# filter.net
KiCad netlist of a schematic drawn in EAGLE
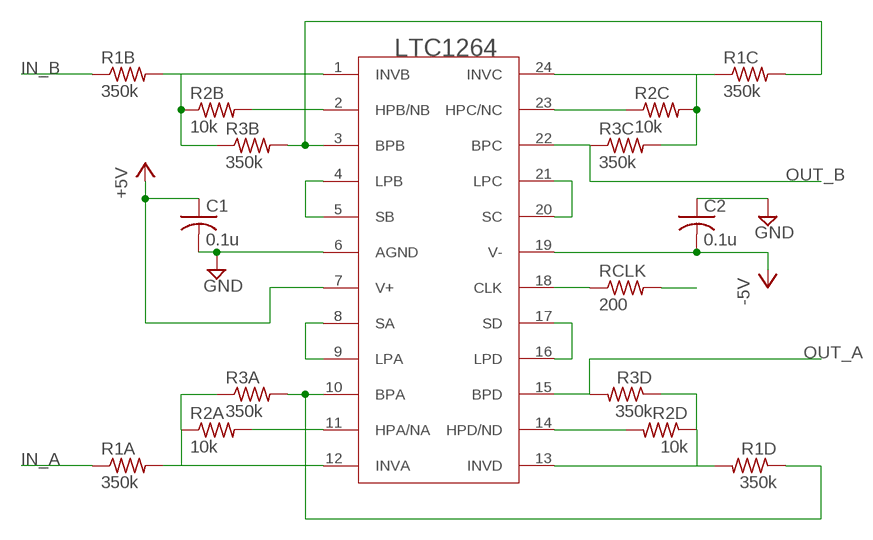
[diagram p0: schematic, sheet 1]

(export (version "E")
  (design (tool "Eeschema 10.0.6"))
  (components
    (comp (ref "C1")
      (value "0.1u")
      (footprint "eagle-import:C0805")
      (libsource (lib "eagle-import") (part "C-USC0805"))
    )
    (comp (ref "C2")
      (value "0.1u")
      (footprint "eagle-import:C0805")
      (libsource (lib "eagle-import") (part "C-USC0805"))
    )
    (comp (ref "R1A")
      (value "350k")
      (footprint "eagle-import:R0805")
      (libsource (lib "eagle-import") (part "R-US_R0805"))
    )
    (comp (ref "R1B")
      (value "350k")
      (footprint "eagle-import:R0805")
      (libsource (lib "eagle-import") (part "R-US_R0805"))
    )
    (comp (ref "R1C")
      (value "350k")
      (footprint "eagle-import:R0805")
      (libsource (lib "eagle-import") (part "R-US_R0805"))
    )
    (comp (ref "R1D")
      (value "350k")
      (footprint "eagle-import:R0805")
      (libsource (lib "eagle-import") (part "R-US_R0805"))
    )
    (comp (ref "R2A")
      (value "10k")
      (footprint "eagle-import:R0805")
      (libsource (lib "eagle-import") (part "R-US_R0805"))
    )
    (comp (ref "R2B")
      (value "10k")
      (footprint "eagle-import:R0805")
      (libsource (lib "eagle-import") (part "R-US_R0805"))
    )
    (comp (ref "R2C")
      (value "10k")
      (footprint "eagle-import:R0805")
      (libsource (lib "eagle-import") (part "R-US_R0805"))
    )
    (comp (ref "R2D")
      (value "10k")
      (footprint "eagle-import:R0805")
      (libsource (lib "eagle-import") (part "R-US_R0805"))
    )
    (comp (ref "R3A")
      (value "350k")
      (footprint "eagle-import:R0805")
      (libsource (lib "eagle-import") (part "R-US_R0805"))
    )
    (comp (ref "R3B")
      (value "350k")
      (footprint "eagle-import:R0805")
      (libsource (lib "eagle-import") (part "R-US_R0805"))
    )
    (comp (ref "R3C")
      (value "350k")
      (footprint "eagle-import:R0805")
      (libsource (lib "eagle-import") (part "R-US_R0805"))
    )
    (comp (ref "R3D")
      (value "350k")
      (footprint "eagle-import:R0805")
      (libsource (lib "eagle-import") (part "R-US_R0805"))
    )
    (comp (ref "RCLK")
      (value "200")
      (footprint "eagle-import:R0805")
      (libsource (lib "eagle-import") (part "R-US_R0805"))
    )
    (comp (ref "U$1")
      (value "LTC1264SMD")
      (footprint "eagle-import:SO24W")
      (libsource (lib "eagle-import") (part "LTC1264SMD"))
    )
  )
  (nets
    (net (code "1") (name "+5V") (class "Default")
      (node (ref "C1") (pin "1") (pinfunction "1_1") (pintype "passive"))
      (node (ref "U$1") (pin "7") (pinfunction "V+_7") (pintype "bidirectional"))
    )
    (net (code "2") (name "-5V") (class "Default")
      (node (ref "C2") (pin "2") (pinfunction "2_2") (pintype "passive"))
      (node (ref "U$1") (pin "19") (pinfunction "V-_19") (pintype "bidirectional"))
    )
    (net (code "3") (name "/IN_A") (class "Default")
      (node (ref "R1A") (pin "1") (pinfunction "1_1") (pintype "passive"))
    )
    (net (code "4") (name "/IN_B") (class "Default")
      (node (ref "R1B") (pin "1") (pinfunction "1_1") (pintype "passive"))
    )
    (net (code "5") (name "/OUT_A") (class "Default")
      (node (ref "R3D") (pin "2") (pinfunction "2_2") (pintype "passive"))
      (node (ref "U$1") (pin "15") (pinfunction "BPD_15") (pintype "bidirectional"))
    )
    (net (code "6") (name "/OUT_B") (class "Default")
      (node (ref "R3C") (pin "1") (pinfunction "1_1") (pintype "passive"))
      (node (ref "U$1") (pin "22") (pinfunction "BPC_22") (pintype "bidirectional"))
    )
    (net (code "7") (name "GND") (class "Default")
      (node (ref "C1") (pin "2") (pinfunction "2_2") (pintype "passive"))
      (node (ref "C2") (pin "1") (pinfunction "1_1") (pintype "passive"))
      (node (ref "U$1") (pin "6") (pinfunction "AGND_6") (pintype "bidirectional"))
    )
    (net (code "8") (name "Net-(U$1-BPA)") (class "Default")
      (node (ref "R1D") (pin "1") (pinfunction "1_1") (pintype "passive"))
      (node (ref "R3A") (pin "2") (pinfunction "2_2") (pintype "passive"))
      (node (ref "U$1") (pin "10") (pinfunction "BPA_10") (pintype "bidirectional"))
    )
    (net (code "9") (name "Net-(U$1-BPB)") (class "Default")
      (node (ref "R1C") (pin "2") (pinfunction "2_2") (pintype "passive"))
      (node (ref "R3B") (pin "2") (pinfunction "2_2") (pintype "passive"))
      (node (ref "U$1") (pin "3") (pinfunction "BPB_3") (pintype "bidirectional"))
    )
    (net (code "10") (name "Net-(U$1-CLK)") (class "Default")
      (node (ref "RCLK") (pin "1") (pinfunction "1_1") (pintype "passive"))
      (node (ref "U$1") (pin "18") (pinfunction "CLK_18") (pintype "bidirectional"))
    )
    (net (code "11") (name "Net-(U$1-HPA{slash}NA)") (class "Default")
      (node (ref "R2A") (pin "2") (pinfunction "2_2") (pintype "passive"))
      (node (ref "U$1") (pin "11") (pinfunction "HPA/NA_11") (pintype "bidirectional"))
    )
    (net (code "12") (name "Net-(U$1-HPB{slash}NB)") (class "Default")
      (node (ref "R2B") (pin "2") (pinfunction "2_2") (pintype "passive"))
      (node (ref "U$1") (pin "2") (pinfunction "HPB/NB_2") (pintype "bidirectional"))
    )
    (net (code "13") (name "Net-(U$1-HPC{slash}NC)") (class "Default")
      (node (ref "R2C") (pin "1") (pinfunction "1_1") (pintype "passive"))
      (node (ref "U$1") (pin "23") (pinfunction "HPC/NC_23") (pintype "bidirectional"))
    )
    (net (code "14") (name "Net-(U$1-HPD{slash}ND)") (class "Default")
      (node (ref "R2D") (pin "2") (pinfunction "2_2") (pintype "passive"))
      (node (ref "U$1") (pin "14") (pinfunction "HPD/ND_14") (pintype "bidirectional"))
    )
    (net (code "15") (name "Net-(U$1-INVA)") (class "Default")
      (node (ref "R1A") (pin "2") (pinfunction "2_2") (pintype "passive"))
      (node (ref "R2A") (pin "1") (pinfunction "1_1") (pintype "passive"))
      (node (ref "R3A") (pin "1") (pinfunction "1_1") (pintype "passive"))
      (node (ref "U$1") (pin "12") (pinfunction "INVA_12") (pintype "bidirectional"))
    )
    (net (code "16") (name "Net-(U$1-INVB)") (class "Default")
      (node (ref "R1B") (pin "2") (pinfunction "2_2") (pintype "passive"))
      (node (ref "R2B") (pin "1") (pinfunction "1_1") (pintype "passive"))
      (node (ref "R3B") (pin "1") (pinfunction "1_1") (pintype "passive"))
      (node (ref "U$1") (pin "1") (pinfunction "INVB_1") (pintype "bidirectional"))
    )
    (net (code "17") (name "Net-(U$1-INVC)") (class "Default")
      (node (ref "R1C") (pin "1") (pinfunction "1_1") (pintype "passive"))
      (node (ref "R2C") (pin "2") (pinfunction "2_2") (pintype "passive"))
      (node (ref "R3C") (pin "2") (pinfunction "2_2") (pintype "passive"))
      (node (ref "U$1") (pin "24") (pinfunction "INVC_24") (pintype "bidirectional"))
    )
    (net (code "18") (name "Net-(U$1-INVD)") (class "Default")
      (node (ref "R1D") (pin "2") (pinfunction "2_2") (pintype "passive"))
      (node (ref "R2D") (pin "1") (pinfunction "1_1") (pintype "passive"))
      (node (ref "R3D") (pin "1") (pinfunction "1_1") (pintype "passive"))
      (node (ref "U$1") (pin "13") (pinfunction "INVD_13") (pintype "bidirectional"))
    )
    (net (code "19") (name "Net-(U$1-LPA)") (class "Default")
      (node (ref "U$1") (pin "8") (pinfunction "SA_8") (pintype "bidirectional"))
      (node (ref "U$1") (pin "9") (pinfunction "LPA_9") (pintype "bidirectional"))
    )
    (net (code "20") (name "Net-(U$1-LPB)") (class "Default")
      (node (ref "U$1") (pin "4") (pinfunction "LPB_4") (pintype "bidirectional"))
      (node (ref "U$1") (pin "5") (pinfunction "SB_5") (pintype "bidirectional"))
    )
    (net (code "21") (name "Net-(U$1-LPC)") (class "Default")
      (node (ref "U$1") (pin "20") (pinfunction "SC_20") (pintype "bidirectional"))
      (node (ref "U$1") (pin "21") (pinfunction "LPC_21") (pintype "bidirectional"))
    )
    (net (code "22") (name "Net-(U$1-LPD)") (class "Default")
      (node (ref "U$1") (pin "16") (pinfunction "LPD_16") (pintype "bidirectional"))
      (node (ref "U$1") (pin "17") (pinfunction "SD_17") (pintype "bidirectional"))
    )
    (net (code "23") (name "unconnected-(RCLK-Pad2)") (class "Default")
      (node (ref "RCLK") (pin "2") (pinfunction "2_2") (pintype "passive"))
    )
  )
)
